# CC_Debugger_Adapter_v1_0.net
KiCad netlist of a schematic drawn in EAGLE
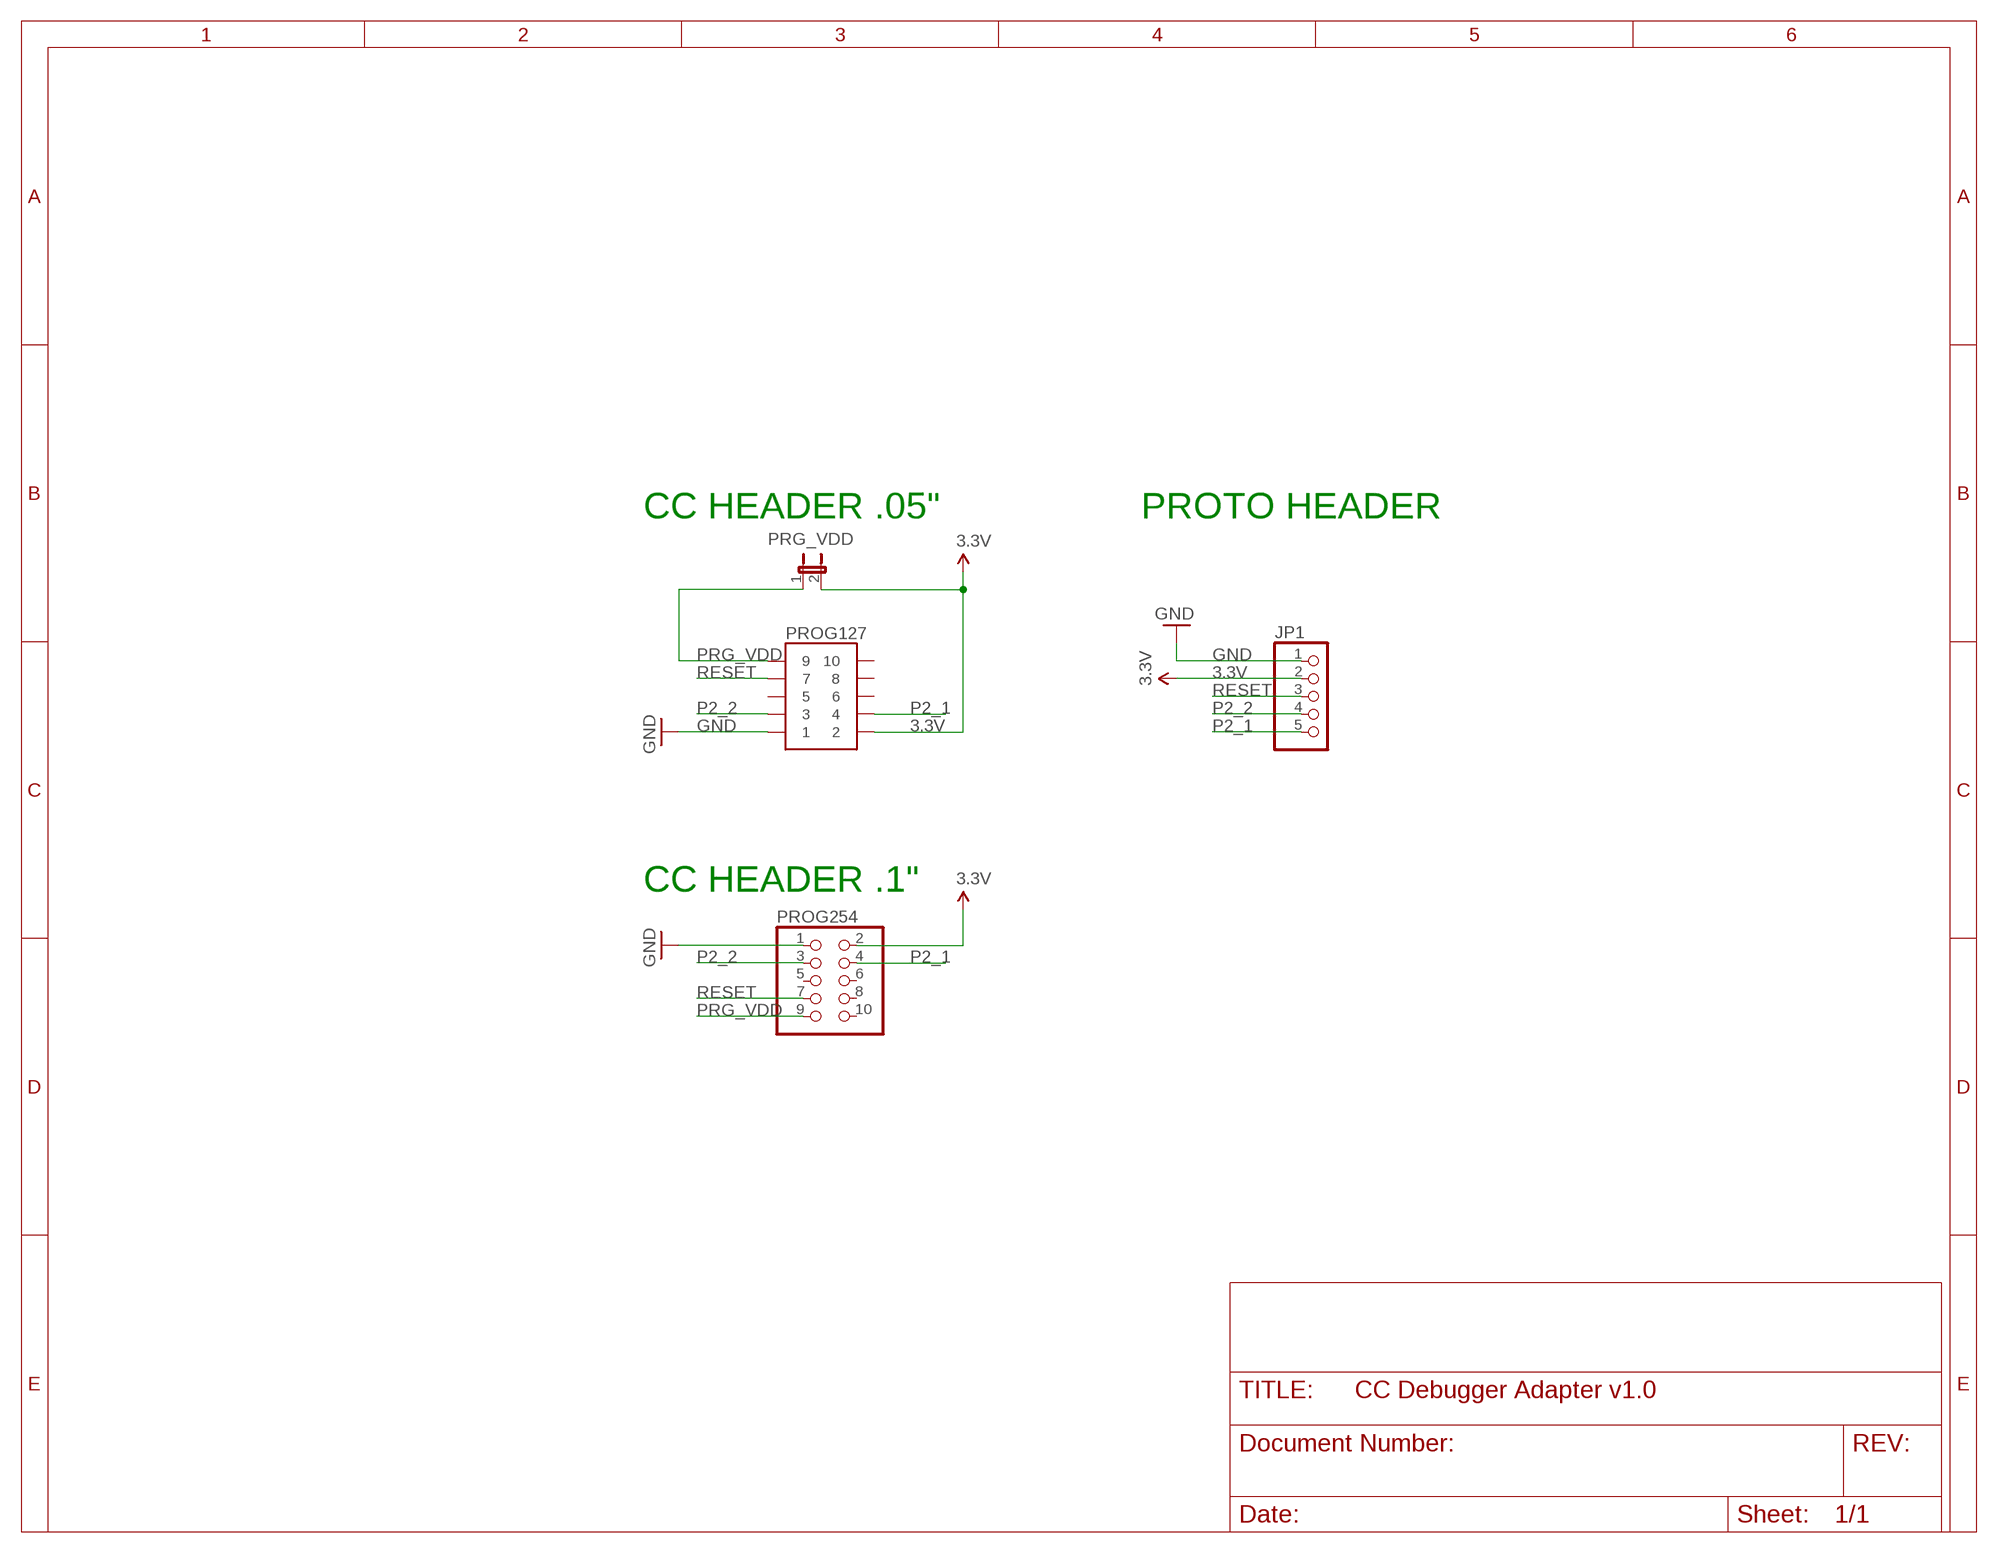
[diagram p0: schematic, sheet 1]

(export (version "E")
  (design (tool "Eeschema 10.0.6"))
  (components
    (comp (ref "JP1")
      (value "PINHD-1X5")
      (footprint "eagle-import:1X05")
      (libsource (lib "eagle-import") (part "PINHD-1X5"))
    )
    (comp (ref "PRG_VDD")
      (value "JUMPER-2PTH")
      (footprint "eagle-import:1X02")
      (libsource (lib "eagle-import") (part "JUMPER-2PTH"))
    )
    (comp (ref "PROG127")
      (value "CONN_5-2-FTSH-V")
      (footprint "eagle-import:FTSH-105-DV")
      (libsource (lib "eagle-import") (part "CONN_5-2-FTSH-V"))
    )
    (comp (ref "PROG254")
      (value "HEADER-2X5")
      (footprint "eagle-import:2X05")
      (libsource (lib "eagle-import") (part "HEADER-2X5"))
    )
  )
  (nets
    (net (code "1") (name "/P2_1") (class "Default")
      (node (ref "JP1") (pin "5") (pinfunction "5_5") (pintype "passive"))
      (node (ref "PROG127") (pin "4") (pinfunction "4_4") (pintype "bidirectional"))
      (node (ref "PROG254") (pin "4") (pinfunction "4_4") (pintype "passive"))
    )
    (net (code "2") (name "/P2_2") (class "Default")
      (node (ref "JP1") (pin "4") (pinfunction "4_4") (pintype "passive"))
      (node (ref "PROG127") (pin "3") (pinfunction "3_3") (pintype "bidirectional"))
      (node (ref "PROG254") (pin "3") (pinfunction "3_3") (pintype "passive"))
    )
    (net (code "3") (name "/PRG_VDD") (class "Default")
      (node (ref "PRG_VDD") (pin "1") (pinfunction "1_1") (pintype "passive"))
      (node (ref "PROG127") (pin "9") (pinfunction "9_9") (pintype "bidirectional"))
      (node (ref "PROG254") (pin "9") (pinfunction "9_9") (pintype "passive"))
    )
    (net (code "4") (name "/RESET") (class "Default")
      (node (ref "JP1") (pin "3") (pinfunction "3_3") (pintype "passive"))
      (node (ref "PROG127") (pin "7") (pinfunction "7_7") (pintype "bidirectional"))
      (node (ref "PROG254") (pin "7") (pinfunction "7_7") (pintype "passive"))
    )
    (net (code "5") (name "3.3V") (class "Default")
      (node (ref "JP1") (pin "2") (pinfunction "2_2") (pintype "passive"))
      (node (ref "PRG_VDD") (pin "2") (pinfunction "2_2") (pintype "passive"))
      (node (ref "PROG127") (pin "2") (pinfunction "2_2") (pintype "bidirectional"))
      (node (ref "PROG254") (pin "2") (pinfunction "2_2") (pintype "passive"))
    )
    (net (code "6") (name "GND") (class "Default")
      (node (ref "JP1") (pin "1") (pinfunction "1_1") (pintype "passive"))
      (node (ref "PROG127") (pin "1") (pinfunction "1_1") (pintype "bidirectional"))
      (node (ref "PROG254") (pin "1") (pinfunction "1_1") (pintype "passive"))
    )
    (net (code "7") (name "unconnected-(PROG127-Pad5)") (class "Default")
      (node (ref "PROG127") (pin "5") (pinfunction "5_5") (pintype "bidirectional"))
    )
    (net (code "8") (name "unconnected-(PROG127-Pad6)") (class "Default")
      (node (ref "PROG127") (pin "6") (pinfunction "6_6") (pintype "bidirectional"))
    )
    (net (code "9") (name "unconnected-(PROG127-Pad8)") (class "Default")
      (node (ref "PROG127") (pin "8") (pinfunction "8_8") (pintype "bidirectional"))
    )
    (net (code "10") (name "unconnected-(PROG127-Pad10)") (class "Default")
      (node (ref "PROG127") (pin "10") (pinfunction "10_10") (pintype "bidirectional"))
    )
    (net (code "11") (name "unconnected-(PROG254-Pad5)") (class "Default")
      (node (ref "PROG254") (pin "5") (pinfunction "5_5") (pintype "passive"))
    )
    (net (code "12") (name "unconnected-(PROG254-Pad6)") (class "Default")
      (node (ref "PROG254") (pin "6") (pinfunction "6_6") (pintype "passive"))
    )
    (net (code "13") (name "unconnected-(PROG254-Pad8)") (class "Default")
      (node (ref "PROG254") (pin "8") (pinfunction "8_8") (pintype "passive"))
    )
    (net (code "14") (name "unconnected-(PROG254-Pad10)") (class "Default")
      (node (ref "PROG254") (pin "10") (pinfunction "10_10") (pintype "passive"))
    )
  )
)
